# DISPLAYPORT.net
KiCad netlist of a schematic drawn in Altium Designer
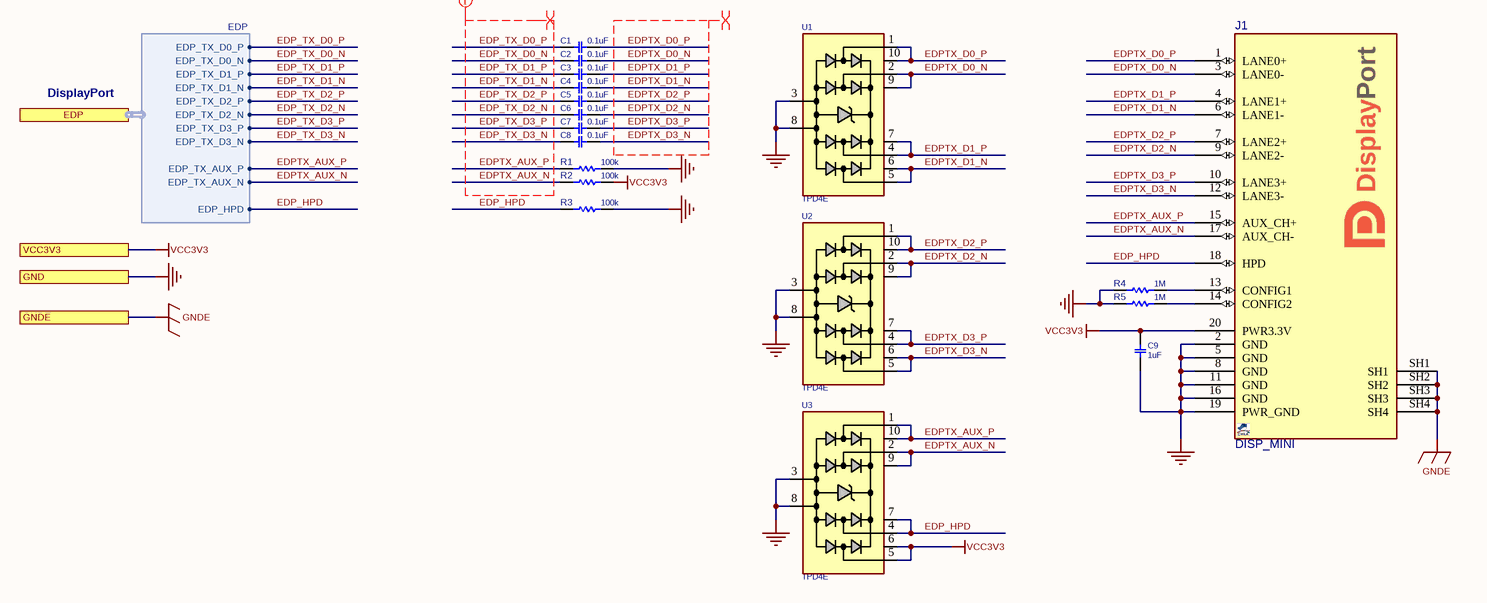
[diagram p0: DISPLAYPORT.SchDoc]

(export (version "E")
  (design (tool "Eeschema 10.0.6"))
  (components
    (comp (ref "C1")
      (value "0.1uF")
      (footprint "C0402O2")
      (description "CAP, MLCC")
      (fields (field (name "MANF_P#") "GRM155R61E104") (field (name "MANF") "Murata"))
      (libsource (lib "passive_smd") (part "CAP_SMD_MLCC"))
    )
    (comp (ref "C2")
      (value "0.1uF")
      (footprint "C0402O2")
      (description "CAP, MLCC")
      (fields (field (name "MANF_P#") "GRM155R61E104") (field (name "MANF") "Murata"))
      (libsource (lib "passive_smd") (part "CAP_SMD_MLCC"))
    )
    (comp (ref "C3")
      (value "0.1uF")
      (footprint "C0402O2")
      (description "CAP, MLCC")
      (fields (field (name "MANF_P#") "GRM155R61E104") (field (name "MANF") "Murata"))
      (libsource (lib "passive_smd") (part "CAP_SMD_MLCC"))
    )
    (comp (ref "C4")
      (value "0.1uF")
      (footprint "C0402O2")
      (description "CAP, MLCC")
      (fields (field (name "MANF_P#") "GRM155R61E104") (field (name "MANF") "Murata"))
      (libsource (lib "passive_smd") (part "CAP_SMD_MLCC"))
    )
    (comp (ref "C5")
      (value "0.1uF")
      (footprint "C0402O2")
      (description "CAP, MLCC")
      (fields (field (name "MANF_P#") "GRM155R61E104") (field (name "MANF") "Murata"))
      (libsource (lib "passive_smd") (part "CAP_SMD_MLCC"))
    )
    (comp (ref "C6")
      (value "0.1uF")
      (footprint "C0402O2")
      (description "CAP, MLCC")
      (fields (field (name "MANF_P#") "GRM155R61E104") (field (name "MANF") "Murata"))
      (libsource (lib "passive_smd") (part "CAP_SMD_MLCC"))
    )
    (comp (ref "C7")
      (value "0.1uF")
      (footprint "C0402O2")
      (description "CAP, MLCC")
      (fields (field (name "MANF_P#") "GRM155R61E104") (field (name "MANF") "Murata"))
      (libsource (lib "passive_smd") (part "CAP_SMD_MLCC"))
    )
    (comp (ref "C8")
      (value "0.1uF")
      (footprint "C0402O2")
      (description "CAP, MLCC")
      (fields (field (name "MANF_P#") "GRM155R61E104") (field (name "MANF") "Murata"))
      (libsource (lib "passive_smd") (part "CAP_SMD_MLCC"))
    )
    (comp (ref "C9")
      (value "1uF")
      (footprint "C0402")
      (description "CAP, MLCC")
      (fields (field (name "MANF_P#") "CL05A105KO5NNND") (field (name "MANF") "Samsung"))
      (libsource (lib "passive_smd") (part "CAP_SMD_MLCC"))
    )
    (comp (ref "J1")
      (value "DISP_MINI")
      (footprint "DISPPORT")
      (description "CONN, Display Port, Right-Angle")
      (fields
        (field (name "MANF") "Molex, JAE")
        (field (name "MANF_P#") "47272-0001, 47272-0024, DP1RD20JQ1R400, DP1RD20JQ2R400")
      )
      (libsource (lib "conn_disp_hdmi") (part "CONN_DISP"))
    )
    (comp (ref "R1")
      (value "100k")
      (footprint "R0402")
      (description "RESISTOR, SMD")
      (libsource (lib "passive_res_smd") (part "RES_SMD"))
    )
    (comp (ref "R2")
      (value "100k")
      (footprint "R0402")
      (description "RESISTOR, SMD")
      (libsource (lib "passive_res_smd") (part "RES_SMD"))
    )
    (comp (ref "R3")
      (value "100k")
      (footprint "R0402")
      (description "RESISTOR, SMD")
      (libsource (lib "passive_res_smd") (part "RES_SMD"))
    )
    (comp (ref "R4")
      (value "1M")
      (footprint "R0402")
      (description "RESISTOR, SMD")
      (libsource (lib "passive_res_smd") (part "RES_SMD"))
    )
    (comp (ref "R5")
      (value "1M")
      (footprint "R0402")
      (description "RESISTOR, SMD")
      (libsource (lib "passive_res_smd") (part "RES_SMD"))
    )
    (comp (ref "U1")
      (value "TPD4E")
      (footprint "SON50_10_2510")
      (description "TVS, ESD PROTECT, 4CH,")
      (fields (field (name "MANF_P#") "TPD4E05U06DQA") (field (name "MANF") "Texas Instruments"))
      (libsource (lib "protect_tvs_esd_fuse") (part "TVS_X4_TPD4E05U06"))
    )
    (comp (ref "U2")
      (value "TPD4E")
      (footprint "SON50_10_2510")
      (description "TVS, ESD PROTECT, 4CH,")
      (fields (field (name "MANF_P#") "TPD4E05U06DQA") (field (name "MANF") "Texas Instruments"))
      (libsource (lib "protect_tvs_esd_fuse") (part "TVS_X4_TPD4E05U06"))
    )
    (comp (ref "U3")
      (value "TPD4E")
      (footprint "SON50_10_2510")
      (description "TVS, ESD PROTECT, 4CH,")
      (fields (field (name "MANF_P#") "TPD4E05U06DQA") (field (name "MANF") "Texas Instruments"))
      (libsource (lib "protect_tvs_esd_fuse") (part "TVS_X4_TPD4E05U06"))
    )
  )
  (nets
    (net (code "2") (name "/EDPTX_AUX_N") (class "Default")
      (node (ref "J1") (pin "17") (pinfunction "AUX_CH-_17") (pintype "bidirectional"))
      (node (ref "R2") (pin "2") (pinfunction "2_2") (pintype "passive"))
      (node (ref "U3") (pin "2") (pinfunction "2_2") (pintype "passive"))
      (node (ref "U3") (pin "9") (pinfunction "9_9") (pintype "passive"))
    )
    (net (code "3") (name "/EDPTX_AUX_P") (class "Default")
      (node (ref "J1") (pin "15") (pinfunction "AUX_CH+_15") (pintype "bidirectional"))
      (node (ref "R1") (pin "2") (pinfunction "2_2") (pintype "passive"))
      (node (ref "U3") (pin "1") (pinfunction "1_1") (pintype "passive"))
      (node (ref "U3") (pin "10") (pinfunction "10_10") (pintype "passive"))
    )
    (net (code "4") (name "/EDPTX_D0_N") (class "Default")
      (node (ref "C2") (pin "2") (pinfunction "2_2") (pintype "passive"))
      (node (ref "J1") (pin "3") (pinfunction "LANE0-_3") (pintype "bidirectional"))
      (node (ref "U1") (pin "2") (pinfunction "2_2") (pintype "passive"))
      (node (ref "U1") (pin "9") (pinfunction "9_9") (pintype "passive"))
    )
    (net (code "5") (name "/EDPTX_D0_P") (class "Default")
      (node (ref "C1") (pin "2") (pinfunction "2_2") (pintype "passive"))
      (node (ref "J1") (pin "1") (pinfunction "LANE0+_1") (pintype "bidirectional"))
      (node (ref "U1") (pin "1") (pinfunction "1_1") (pintype "passive"))
      (node (ref "U1") (pin "10") (pinfunction "10_10") (pintype "passive"))
    )
    (net (code "6") (name "/EDPTX_D1_N") (class "Default")
      (node (ref "C4") (pin "2") (pinfunction "2_2") (pintype "passive"))
      (node (ref "J1") (pin "6") (pinfunction "LANE1-_6") (pintype "bidirectional"))
      (node (ref "U1") (pin "5") (pinfunction "5_5") (pintype "passive"))
      (node (ref "U1") (pin "6") (pinfunction "6_6") (pintype "passive"))
    )
    (net (code "7") (name "/EDPTX_D1_P") (class "Default")
      (node (ref "C3") (pin "2") (pinfunction "2_2") (pintype "passive"))
      (node (ref "J1") (pin "4") (pinfunction "LANE1+_4") (pintype "bidirectional"))
      (node (ref "U1") (pin "4") (pinfunction "4_4") (pintype "passive"))
      (node (ref "U1") (pin "7") (pinfunction "7_7") (pintype "passive"))
    )
    (net (code "8") (name "/EDPTX_D2_N") (class "Default")
      (node (ref "C6") (pin "2") (pinfunction "2_2") (pintype "passive"))
      (node (ref "J1") (pin "9") (pinfunction "LANE2-_9") (pintype "bidirectional"))
      (node (ref "U2") (pin "2") (pinfunction "2_2") (pintype "passive"))
      (node (ref "U2") (pin "9") (pinfunction "9_9") (pintype "passive"))
    )
    (net (code "9") (name "/EDPTX_D2_P") (class "Default")
      (node (ref "C5") (pin "2") (pinfunction "2_2") (pintype "passive"))
      (node (ref "J1") (pin "7") (pinfunction "LANE2+_7") (pintype "bidirectional"))
      (node (ref "U2") (pin "1") (pinfunction "1_1") (pintype "passive"))
      (node (ref "U2") (pin "10") (pinfunction "10_10") (pintype "passive"))
    )
    (net (code "10") (name "/EDPTX_D3_N") (class "Default")
      (node (ref "C8") (pin "2") (pinfunction "2_2") (pintype "passive"))
      (node (ref "J1") (pin "12") (pinfunction "LANE3-_12") (pintype "bidirectional"))
      (node (ref "U2") (pin "5") (pinfunction "5_5") (pintype "passive"))
      (node (ref "U2") (pin "6") (pinfunction "6_6") (pintype "passive"))
    )
    (net (code "11") (name "/EDPTX_D3_P") (class "Default")
      (node (ref "C7") (pin "2") (pinfunction "2_2") (pintype "passive"))
      (node (ref "J1") (pin "10") (pinfunction "LANE3+_10") (pintype "bidirectional"))
      (node (ref "U2") (pin "4") (pinfunction "4_4") (pintype "passive"))
      (node (ref "U2") (pin "7") (pinfunction "7_7") (pintype "passive"))
    )
    (net (code "12") (name "/EDP_HPD") (class "Default")
      (node (ref "J1") (pin "18") (pinfunction "HPD_18") (pintype "bidirectional"))
      (node (ref "R3") (pin "2") (pinfunction "2_2") (pintype "passive"))
      (node (ref "U3") (pin "4") (pinfunction "4_4") (pintype "passive"))
      (node (ref "U3") (pin "7") (pinfunction "7_7") (pintype "passive"))
    )
    (net (code "13") (name "/EDP_TX_D0_N") (class "Default")
      (node (ref "C2") (pin "1") (pinfunction "1_1") (pintype "passive"))
    )
    (net (code "14") (name "/EDP_TX_D0_P") (class "Default")
      (node (ref "C1") (pin "1") (pinfunction "1_1") (pintype "passive"))
    )
    (net (code "15") (name "/EDP_TX_D1_N") (class "Default")
      (node (ref "C4") (pin "1") (pinfunction "1_1") (pintype "passive"))
    )
    (net (code "16") (name "/EDP_TX_D1_P") (class "Default")
      (node (ref "C3") (pin "1") (pinfunction "1_1") (pintype "passive"))
    )
    (net (code "17") (name "/EDP_TX_D2_N") (class "Default")
      (node (ref "C6") (pin "1") (pinfunction "1_1") (pintype "passive"))
    )
    (net (code "18") (name "/EDP_TX_D2_P") (class "Default")
      (node (ref "C5") (pin "1") (pinfunction "1_1") (pintype "passive"))
    )
    (net (code "19") (name "/EDP_TX_D3_N") (class "Default")
      (node (ref "C8") (pin "1") (pinfunction "1_1") (pintype "passive"))
    )
    (net (code "20") (name "/EDP_TX_D3_P") (class "Default")
      (node (ref "C7") (pin "1") (pinfunction "1_1") (pintype "passive"))
    )
    (net (code "22") (name "GND") (class "Default")
      (node (ref "C9") (pin "2") (pinfunction "2_2") (pintype "passive"))
      (node (ref "J1") (pin "11") (pinfunction "GND_11") (pintype "passive"))
      (node (ref "J1") (pin "16") (pinfunction "GND_16") (pintype "passive"))
      (node (ref "J1") (pin "19") (pinfunction "PWR_GND_19") (pintype "passive"))
      (node (ref "J1") (pin "2") (pinfunction "GND_2") (pintype "passive"))
      (node (ref "J1") (pin "5") (pinfunction "GND_5") (pintype "passive"))
      (node (ref "J1") (pin "8") (pinfunction "GND_8") (pintype "passive"))
      (node (ref "R1") (pin "1") (pinfunction "1_1") (pintype "passive"))
      (node (ref "R3") (pin "1") (pinfunction "1_1") (pintype "passive"))
      (node (ref "R4") (pin "2") (pinfunction "2_2") (pintype "passive"))
      (node (ref "R5") (pin "2") (pinfunction "2_2") (pintype "passive"))
      (node (ref "U1") (pin "3") (pinfunction "3_3") (pintype "passive"))
      (node (ref "U1") (pin "8") (pinfunction "8_8") (pintype "passive"))
      (node (ref "U2") (pin "3") (pinfunction "3_3") (pintype "passive"))
      (node (ref "U2") (pin "8") (pinfunction "8_8") (pintype "passive"))
      (node (ref "U3") (pin "3") (pinfunction "3_3") (pintype "passive"))
      (node (ref "U3") (pin "8") (pinfunction "8_8") (pintype "passive"))
    )
    (net (code "23") (name "GNDE") (class "Default")
      (node (ref "J1") (pin "SH1") (pinfunction "SH1_SH1") (pintype "passive"))
      (node (ref "J1") (pin "SH2") (pinfunction "SH2_SH2") (pintype "passive"))
      (node (ref "J1") (pin "SH3") (pinfunction "SH3_SH3") (pintype "passive"))
      (node (ref "J1") (pin "SH4") (pinfunction "SH4_SH4") (pintype "passive"))
    )
    (net (code "24") (name "Net-(J1-CONFIG1)") (class "Default")
      (node (ref "J1") (pin "13") (pinfunction "CONFIG1_13") (pintype "bidirectional"))
      (node (ref "R4") (pin "1") (pinfunction "1_1") (pintype "passive"))
    )
    (net (code "25") (name "Net-(J1-CONFIG2)") (class "Default")
      (node (ref "J1") (pin "14") (pinfunction "CONFIG2_14") (pintype "bidirectional"))
      (node (ref "R5") (pin "1") (pinfunction "1_1") (pintype "passive"))
    )
    (net (code "26") (name "VCC3V3") (class "Default")
      (node (ref "C9") (pin "1") (pinfunction "1_1") (pintype "passive"))
      (node (ref "J1") (pin "20") (pinfunction "PWR3.3V_20") (pintype "passive"))
      (node (ref "R2") (pin "1") (pinfunction "1_1") (pintype "passive"))
      (node (ref "U3") (pin "5") (pinfunction "5_5") (pintype "passive"))
      (node (ref "U3") (pin "6") (pinfunction "6_6") (pintype "passive"))
    )
  )
)
